# musicbusinesscard.net
KiCad netlist of a schematic drawn in EAGLE
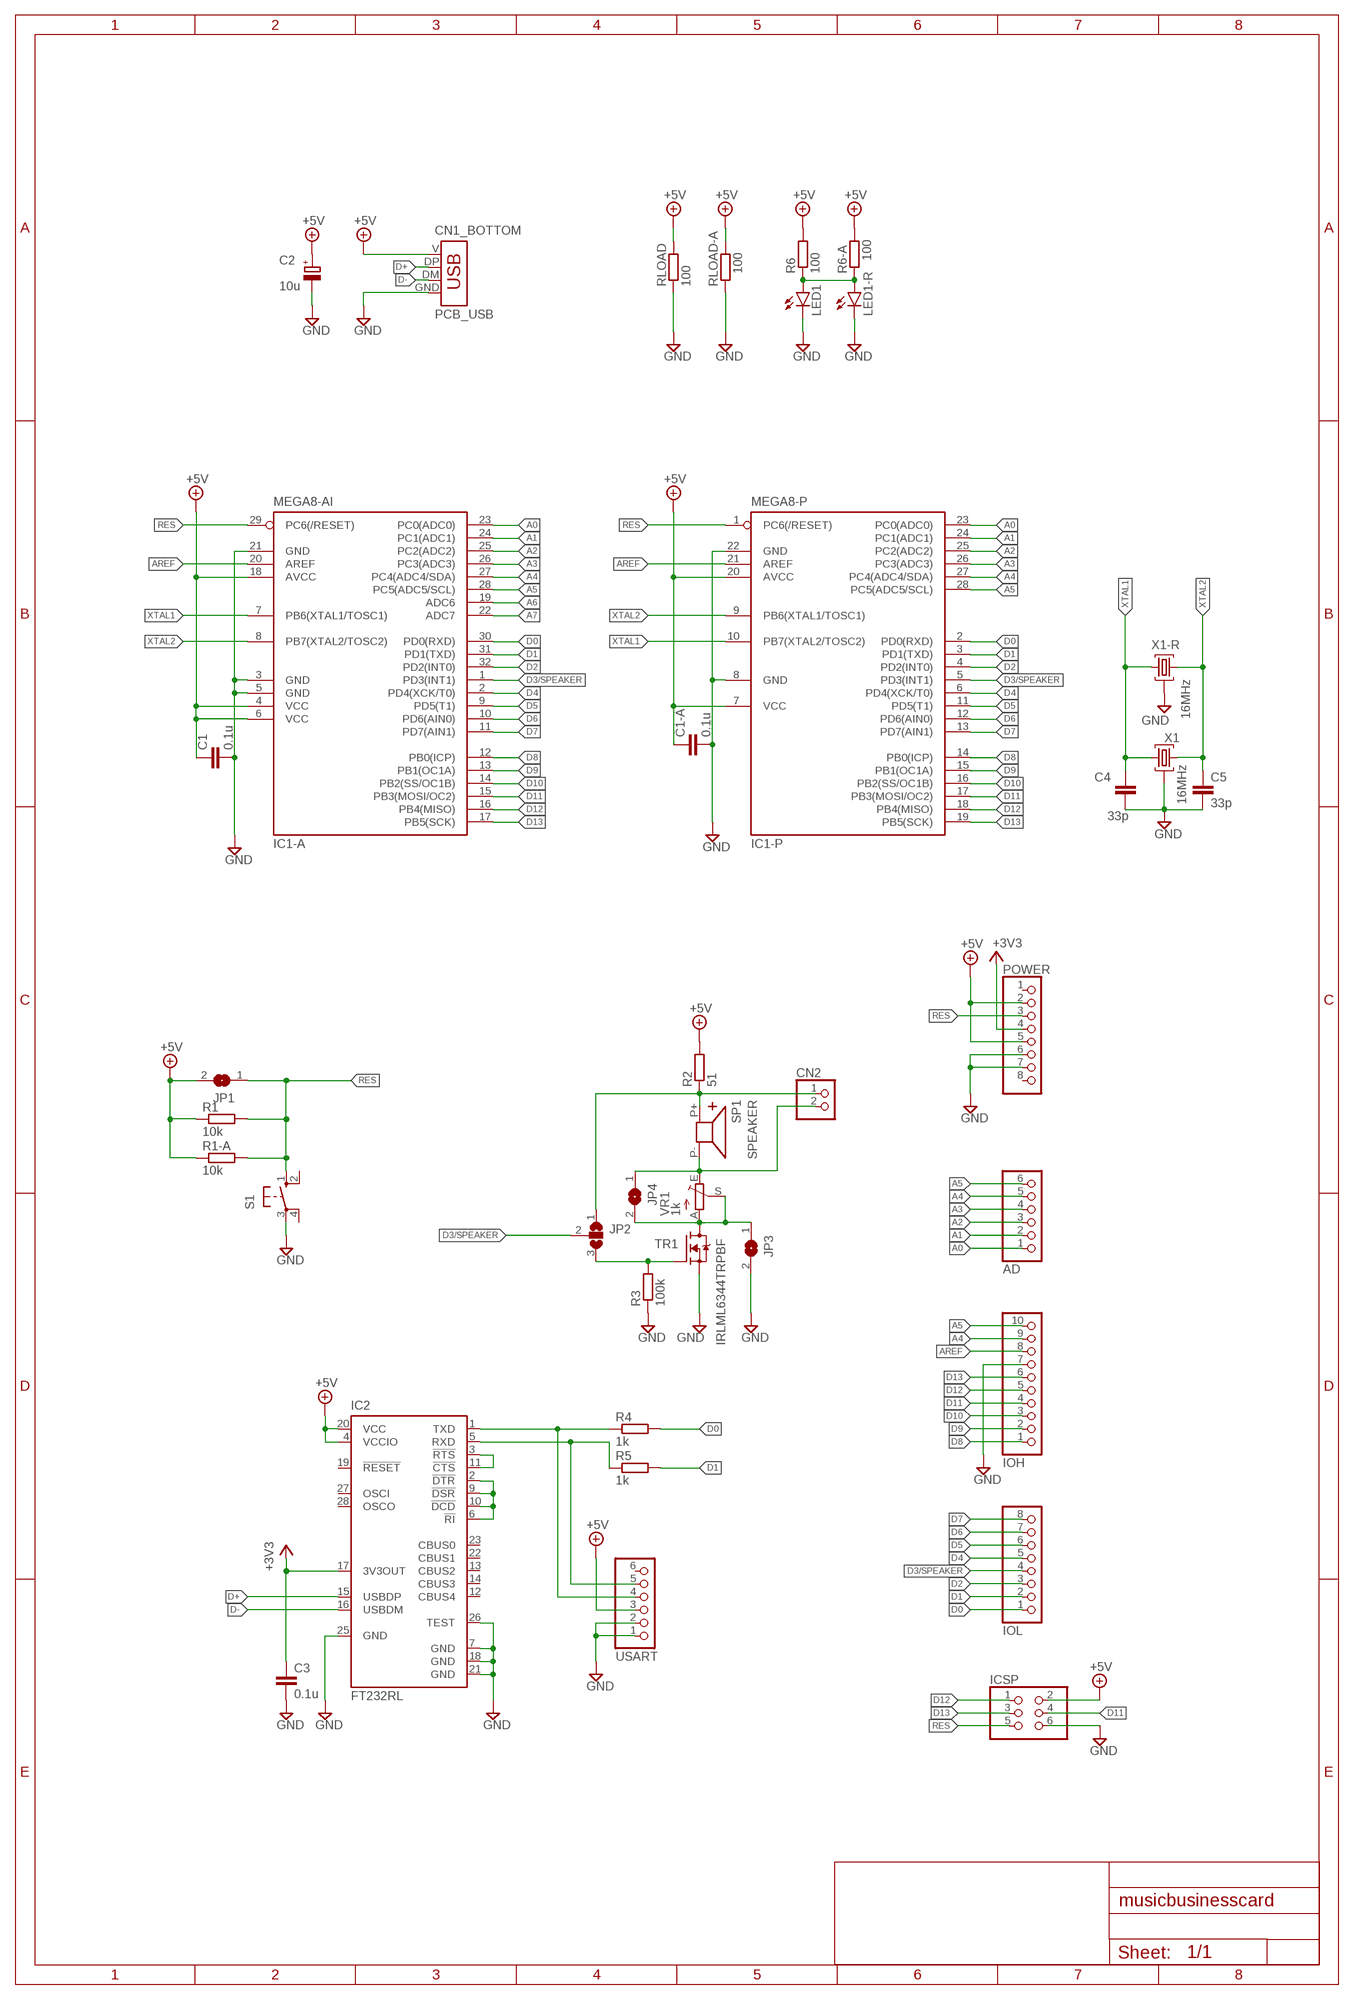
[diagram p0: schematic, sheet 1]

(export (version "E")
  (design (tool "Eeschema 10.0.6"))
  (components
    (comp (ref "AD")
      (value "PINHD-1X6")
      (footprint "eagle-import:1X06")
      (libsource (lib "eagle-import") (part "PINHD-1X6"))
    )
    (comp (ref "C1")
      (value "0.1u")
      (footprint "eagle-import:C3216")
      (libsource (lib "eagle-import") (part "C-EUC3216"))
    )
    (comp (ref "C1-A")
      (value "0.1u")
      (footprint "eagle-import:C050-024X044")
      (libsource (lib "eagle-import") (part "C-EU050-024X044"))
    )
    (comp (ref "C2")
      (value "10u")
      (footprint "eagle-import:TT2D5")
      (libsource (lib "eagle-import") (part "CPOL-EUTT2D5"))
    )
    (comp (ref "C3")
      (value "0.1u")
      (footprint "eagle-import:C3216")
      (libsource (lib "eagle-import") (part "C-EUC3216"))
    )
    (comp (ref "C4")
      (value "33p")
      (footprint "eagle-import:C050-024X044")
      (libsource (lib "eagle-import") (part "C-EU050-024X044"))
    )
    (comp (ref "C5")
      (value "33p")
      (footprint "eagle-import:C050-024X044")
      (libsource (lib "eagle-import") (part "C-EU050-024X044"))
    )
    (comp (ref "CN1_BOTTOM")
      (value "PCB_USB")
      (footprint "eagle-import:PCB_USB")
      (libsource (lib "eagle-import") (part "PCB_USB"))
    )
    (comp (ref "CN2")
      (value "PINHD-1X2")
      (footprint "eagle-import:1X02")
      (libsource (lib "eagle-import") (part "PINHD-1X2"))
    )
    (comp (ref "IC1-A")
      (value "MEGA8-AI")
      (footprint "eagle-import:TQFP32-08")
      (fields (field (name "MPN") "ATMEGA8-16AU"))
      (libsource (lib "eagle-import") (part "MEGA8-AI"))
    )
    (comp (ref "IC1-P")
      (value "MEGA8-P")
      (footprint "eagle-import:DIL28-3")
      (libsource (lib "eagle-import") (part "MEGA8-P"))
    )
    (comp (ref "IC2")
      (value "FT232RL")
      (footprint "eagle-import:SSOP28")
      (libsource (lib "eagle-import") (part "FT232RL"))
    )
    (comp (ref "ICSP")
      (value "PINHD-2X3")
      (footprint "eagle-import:2X03")
      (libsource (lib "eagle-import") (part "PINHD-2X3"))
    )
    (comp (ref "IOH")
      (value "PINHD-1X10")
      (footprint "eagle-import:1X10")
      (libsource (lib "eagle-import") (part "PINHD-1X10"))
    )
    (comp (ref "IOL")
      (value "PINHD-1X8")
      (footprint "eagle-import:1X08")
      (libsource (lib "eagle-import") (part "PINHD-1X8"))
    )
    (comp (ref "JP1") (value "SJ") (footprint "eagle-import:SJ") (libsource (lib "eagle-import") (part "SJ")))
    (comp (ref "JP2")
      (value "SJ2W")
      (footprint "eagle-import:SJ_2")
      (libsource (lib "eagle-import") (part "SJ2W"))
    )
    (comp (ref "JP3") (value "SJ") (footprint "eagle-import:SJ") (libsource (lib "eagle-import") (part "SJ")))
    (comp (ref "JP4") (value "SJ") (footprint "eagle-import:SJ") (libsource (lib "eagle-import") (part "SJ")))
    (comp (ref "LED1")
      (value "LEDCHIPLED_1206")
      (footprint "eagle-import:CHIPLED_1206")
      (libsource (lib "eagle-import") (part "LEDCHIPLED_1206"))
    )
    (comp (ref "LED1-R")
      (value "LED3MM")
      (footprint "eagle-import:LED3MM")
      (libsource (lib "eagle-import") (part "LED3MM"))
    )
    (comp (ref "POWER")
      (value "PINHD-1X8")
      (footprint "eagle-import:1X08")
      (libsource (lib "eagle-import") (part "PINHD-1X8"))
    )
    (comp (ref "R1")
      (value "10k")
      (footprint "eagle-import:R3216")
      (libsource (lib "eagle-import") (part "R-EU_R3216"))
    )
    (comp (ref "R1-A")
      (value "10k")
      (footprint "eagle-import:0207_10")
      (libsource (lib "eagle-import") (part "R-EU_0207/10"))
    )
    (comp (ref "R2")
      (value "51")
      (footprint "eagle-import:R3216")
      (libsource (lib "eagle-import") (part "R-EU_R3216"))
    )
    (comp (ref "R3")
      (value "100k")
      (footprint "eagle-import:R3216")
      (libsource (lib "eagle-import") (part "R-EU_R3216"))
    )
    (comp (ref "R4")
      (value "1k")
      (footprint "eagle-import:R3216")
      (libsource (lib "eagle-import") (part "R-EU_R3216"))
    )
    (comp (ref "R5")
      (value "1k")
      (footprint "eagle-import:R3216")
      (libsource (lib "eagle-import") (part "R-EU_R3216"))
    )
    (comp (ref "R6")
      (value "100")
      (footprint "eagle-import:R3216")
      (libsource (lib "eagle-import") (part "R-EU_R3216"))
    )
    (comp (ref "R6-A")
      (value "100")
      (footprint "eagle-import:0207_10")
      (libsource (lib "eagle-import") (part "R-EU_0207/10"))
    )
    (comp (ref "RLOAD")
      (value "100")
      (footprint "eagle-import:R3216")
      (libsource (lib "eagle-import") (part "R-EU_R3216"))
    )
    (comp (ref "RLOAD-A")
      (value "100")
      (footprint "eagle-import:0207_10")
      (libsource (lib "eagle-import") (part "R-EU_0207/10"))
    )
    (comp (ref "S1")
      (value "10-XX")
      (footprint "eagle-import:B3F-10XX")
      (fields (field (name "MPN") "B3F-1000"))
      (libsource (lib "eagle-import") (part "10-XX"))
    )
    (comp (ref "SP1")
      (value "SPEAKER")
      (footprint "eagle-import:SPEAKER")
      (libsource (lib "eagle-import") (part "SPEAKER"))
    )
    (comp (ref "TR1")
      (value "IRLML6344TRPBF")
      (footprint "eagle-import:SOT23")
      (libsource (lib "eagle-import") (part "IRLML6344TRPBF"))
    )
    (comp (ref "USART")
      (value "PINHD-1X6")
      (footprint "eagle-import:1X06")
      (libsource (lib "eagle-import") (part "PINHD-1X6"))
    )
    (comp (ref "VR1")
      (value "1k")
      (footprint "eagle-import:B25P")
      (libsource (lib "eagle-import") (part "TRIM_EU-B25P"))
    )
    (comp (ref "X1")
      (value "16MHz")
      (footprint "eagle-import:XTAL_MURATA")
      (libsource (lib "eagle-import") (part "XTAL_MURATA"))
    )
    (comp (ref "X1-R")
      (value "16MHz")
      (footprint "eagle-import:HC49U")
      (libsource (lib "eagle-import") (part "14M20BHC49T"))
    )
  )
  (nets
    (net (code "1") (name "+3V3") (class "Default")
      (node (ref "C3") (pin "1") (pinfunction "1_1") (pintype "passive"))
      (node (ref "IC2") (pin "17") (pinfunction "3V3OUT_17") (pintype "output"))
      (node (ref "POWER") (pin "4") (pinfunction "4_4") (pintype "passive"))
    )
    (net (code "2") (name "+5V") (class "Default")
      (node (ref "C1") (pin "1") (pinfunction "1_1") (pintype "passive"))
      (node (ref "C1-A") (pin "1") (pinfunction "1_1") (pintype "passive"))
      (node (ref "C2") (pin "+") (pinfunction "+_+") (pintype "passive"))
      (node (ref "CN1_BOTTOM") (pin "V") (pinfunction "1_V") (pintype "passive"))
      (node (ref "IC1-A") (pin "18") (pinfunction "AVCC_18") (pintype "power_in"))
      (node (ref "IC1-A") (pin "4") (pinfunction "VCC_4") (pintype "power_in"))
      (node (ref "IC1-A") (pin "6") (pinfunction "VCC_6") (pintype "power_in"))
      (node (ref "IC1-P") (pin "20") (pinfunction "AVCC_20") (pintype "power_in"))
      (node (ref "IC1-P") (pin "7") (pinfunction "VCC_7") (pintype "power_in"))
      (node (ref "IC2") (pin "20") (pinfunction "VCC_20") (pintype "power_in"))
      (node (ref "IC2") (pin "4") (pinfunction "VCCIO_4") (pintype "power_in"))
      (node (ref "ICSP") (pin "2") (pinfunction "2_2") (pintype "passive"))
      (node (ref "JP1") (pin "2") (pinfunction "2_2") (pintype "passive"))
      (node (ref "POWER") (pin "2") (pinfunction "2_2") (pintype "passive"))
      (node (ref "POWER") (pin "5") (pinfunction "5_5") (pintype "passive"))
      (node (ref "R1") (pin "1") (pinfunction "1_1") (pintype "passive"))
      (node (ref "R1-A") (pin "1") (pinfunction "1_1") (pintype "passive"))
      (node (ref "R2") (pin "2") (pinfunction "2_2") (pintype "passive"))
      (node (ref "R6") (pin "2") (pinfunction "2_2") (pintype "passive"))
      (node (ref "R6-A") (pin "2") (pinfunction "2_2") (pintype "passive"))
      (node (ref "RLOAD") (pin "2") (pinfunction "2_2") (pintype "passive"))
      (node (ref "RLOAD-A") (pin "2") (pinfunction "2_2") (pintype "passive"))
      (node (ref "USART") (pin "3") (pinfunction "3_3") (pintype "passive"))
    )
    (net (code "3") (name "A0") (class "Default")
      (node (ref "AD") (pin "1") (pinfunction "1_1") (pintype "passive"))
      (node (ref "IC1-A") (pin "23") (pinfunction "PC0(ADC0)_23") (pintype "bidirectional"))
      (node (ref "IC1-P") (pin "23") (pinfunction "PC0(ADC0)_23") (pintype "bidirectional"))
    )
    (net (code "4") (name "A1") (class "Default")
      (node (ref "AD") (pin "2") (pinfunction "2_2") (pintype "passive"))
      (node (ref "IC1-A") (pin "24") (pinfunction "PC1(ADC1)_24") (pintype "bidirectional"))
      (node (ref "IC1-P") (pin "24") (pinfunction "PC1(ADC1)_24") (pintype "bidirectional"))
    )
    (net (code "5") (name "A2") (class "Default")
      (node (ref "AD") (pin "3") (pinfunction "3_3") (pintype "passive"))
      (node (ref "IC1-A") (pin "25") (pinfunction "PC2(ADC2)_25") (pintype "bidirectional"))
      (node (ref "IC1-P") (pin "25") (pinfunction "PC2(ADC2)_25") (pintype "bidirectional"))
    )
    (net (code "6") (name "A3") (class "Default")
      (node (ref "AD") (pin "4") (pinfunction "4_4") (pintype "passive"))
      (node (ref "IC1-A") (pin "26") (pinfunction "PC3(ADC3)_26") (pintype "bidirectional"))
      (node (ref "IC1-P") (pin "26") (pinfunction "PC3(ADC3)_26") (pintype "bidirectional"))
    )
    (net (code "7") (name "A4") (class "Default")
      (node (ref "AD") (pin "5") (pinfunction "5_5") (pintype "passive"))
      (node (ref "IC1-A") (pin "27") (pinfunction "PC4(ADC4/SDA)_27") (pintype "bidirectional"))
      (node (ref "IC1-P") (pin "27") (pinfunction "PC4(ADC4/SDA)_27") (pintype "bidirectional"))
      (node (ref "IOH") (pin "9") (pinfunction "9_9") (pintype "passive"))
    )
    (net (code "8") (name "A5") (class "Default")
      (node (ref "AD") (pin "6") (pinfunction "6_6") (pintype "passive"))
      (node (ref "IC1-A") (pin "28") (pinfunction "PC5(ADC5/SCL)_28") (pintype "bidirectional"))
      (node (ref "IC1-P") (pin "28") (pinfunction "PC5(ADC5/SCL)_28") (pintype "bidirectional"))
      (node (ref "IOH") (pin "10") (pinfunction "10_10") (pintype "passive"))
    )
    (net (code "9") (name "A6") (class "Default")
      (node (ref "IC1-A") (pin "19") (pinfunction "ADC6_19") (pintype "bidirectional"))
    )
    (net (code "10") (name "A7") (class "Default")
      (node (ref "IC1-A") (pin "22") (pinfunction "ADC7_22") (pintype "bidirectional"))
    )
    (net (code "11") (name "AREF") (class "Default")
      (node (ref "IC1-A") (pin "20") (pinfunction "AREF_20") (pintype "passive"))
      (node (ref "IC1-P") (pin "21") (pinfunction "AREF_21") (pintype "passive"))
      (node (ref "IOH") (pin "8") (pinfunction "8_8") (pintype "passive"))
    )
    (net (code "12") (name "D+") (class "Default")
      (node (ref "CN1_BOTTOM") (pin "DP") (pinfunction "2_DP") (pintype "passive"))
      (node (ref "IC2") (pin "15") (pinfunction "USBDP_15") (pintype "bidirectional"))
    )
    (net (code "13") (name "D-") (class "Default")
      (node (ref "CN1_BOTTOM") (pin "DM") (pinfunction "3_DM") (pintype "passive"))
      (node (ref "IC2") (pin "16") (pinfunction "USBDM_16") (pintype "bidirectional"))
    )
    (net (code "14") (name "D0") (class "Default")
      (node (ref "IC1-A") (pin "30") (pinfunction "PD0(RXD)_30") (pintype "bidirectional"))
      (node (ref "IC1-P") (pin "2") (pinfunction "PD0(RXD)_2") (pintype "bidirectional"))
      (node (ref "IOL") (pin "1") (pinfunction "1_1") (pintype "passive"))
      (node (ref "R4") (pin "2") (pinfunction "2_2") (pintype "passive"))
    )
    (net (code "15") (name "D1") (class "Default")
      (node (ref "IC1-A") (pin "31") (pinfunction "PD1(TXD)_31") (pintype "bidirectional"))
      (node (ref "IC1-P") (pin "3") (pinfunction "PD1(TXD)_3") (pintype "bidirectional"))
      (node (ref "IOL") (pin "2") (pinfunction "2_2") (pintype "passive"))
      (node (ref "R5") (pin "2") (pinfunction "2_2") (pintype "passive"))
    )
    (net (code "16") (name "D2") (class "Default")
      (node (ref "IC1-A") (pin "32") (pinfunction "PD2(INT0)_32") (pintype "bidirectional"))
      (node (ref "IC1-P") (pin "4") (pinfunction "PD2(INT0)_4") (pintype "bidirectional"))
      (node (ref "IOL") (pin "3") (pinfunction "3_3") (pintype "passive"))
    )
    (net (code "17") (name "D3{slash}SPEAKER") (class "Default")
      (node (ref "IC1-A") (pin "1") (pinfunction "PD3(INT1)_1") (pintype "bidirectional"))
      (node (ref "IC1-P") (pin "5") (pinfunction "PD3(INT1)_5") (pintype "bidirectional"))
      (node (ref "IOL") (pin "4") (pinfunction "4_4") (pintype "passive"))
      (node (ref "JP2") (pin "2") (pinfunction "2_2") (pintype "passive"))
    )
    (net (code "18") (name "D4") (class "Default")
      (node (ref "IC1-A") (pin "2") (pinfunction "PD4(XCK/T0)_2") (pintype "bidirectional"))
      (node (ref "IC1-P") (pin "6") (pinfunction "PD4(XCK/T0)_6") (pintype "bidirectional"))
      (node (ref "IOL") (pin "5") (pinfunction "5_5") (pintype "passive"))
    )
    (net (code "19") (name "D5") (class "Default")
      (node (ref "IC1-A") (pin "9") (pinfunction "PD5(T1)_9") (pintype "bidirectional"))
      (node (ref "IC1-P") (pin "11") (pinfunction "PD5(T1)_11") (pintype "bidirectional"))
      (node (ref "IOL") (pin "6") (pinfunction "6_6") (pintype "passive"))
    )
    (net (code "20") (name "D6") (class "Default")
      (node (ref "IC1-A") (pin "10") (pinfunction "PD6(AIN0)_10") (pintype "bidirectional"))
      (node (ref "IC1-P") (pin "12") (pinfunction "PD6(AIN0)_12") (pintype "bidirectional"))
      (node (ref "IOL") (pin "7") (pinfunction "7_7") (pintype "passive"))
    )
    (net (code "21") (name "D7") (class "Default")
      (node (ref "IC1-A") (pin "11") (pinfunction "PD7(AIN1)_11") (pintype "bidirectional"))
      (node (ref "IC1-P") (pin "13") (pinfunction "PD7(AIN1)_13") (pintype "bidirectional"))
      (node (ref "IOL") (pin "8") (pinfunction "8_8") (pintype "passive"))
    )
    (net (code "22") (name "D8") (class "Default")
      (node (ref "IC1-A") (pin "12") (pinfunction "PB0(ICP)_12") (pintype "bidirectional"))
      (node (ref "IC1-P") (pin "14") (pinfunction "PB0(ICP)_14") (pintype "bidirectional"))
      (node (ref "IOH") (pin "1") (pinfunction "1_1") (pintype "passive"))
    )
    (net (code "23") (name "D9") (class "Default")
      (node (ref "IC1-A") (pin "13") (pinfunction "PB1(OC1A)_13") (pintype "bidirectional"))
      (node (ref "IC1-P") (pin "15") (pinfunction "PB1(OC1A)_15") (pintype "bidirectional"))
      (node (ref "IOH") (pin "2") (pinfunction "2_2") (pintype "passive"))
    )
    (net (code "24") (name "D10") (class "Default")
      (node (ref "IC1-A") (pin "14") (pinfunction "PB2(SS/OC1B)_14") (pintype "bidirectional"))
      (node (ref "IC1-P") (pin "16") (pinfunction "PB2(SS/OC1B)_16") (pintype "bidirectional"))
      (node (ref "IOH") (pin "3") (pinfunction "3_3") (pintype "passive"))
    )
    (net (code "25") (name "D11") (class "Default")
      (node (ref "IC1-A") (pin "15") (pinfunction "PB3(MOSI/OC2)_15") (pintype "bidirectional"))
      (node (ref "IC1-P") (pin "17") (pinfunction "PB3(MOSI/OC2)_17") (pintype "bidirectional"))
      (node (ref "ICSP") (pin "4") (pinfunction "4_4") (pintype "passive"))
      (node (ref "IOH") (pin "4") (pinfunction "4_4") (pintype "passive"))
    )
    (net (code "26") (name "D12") (class "Default")
      (node (ref "IC1-A") (pin "16") (pinfunction "PB4(MISO)_16") (pintype "bidirectional"))
      (node (ref "IC1-P") (pin "18") (pinfunction "PB4(MISO)_18") (pintype "bidirectional"))
      (node (ref "ICSP") (pin "1") (pinfunction "1_1") (pintype "passive"))
      (node (ref "IOH") (pin "5") (pinfunction "5_5") (pintype "passive"))
    )
    (net (code "27") (name "D13") (class "Default")
      (node (ref "IC1-A") (pin "17") (pinfunction "PB5(SCK)_17") (pintype "bidirectional"))
      (node (ref "IC1-P") (pin "19") (pinfunction "PB5(SCK)_19") (pintype "bidirectional"))
      (node (ref "ICSP") (pin "3") (pinfunction "3_3") (pintype "passive"))
      (node (ref "IOH") (pin "6") (pinfunction "6_6") (pintype "passive"))
    )
    (net (code "28") (name "GND") (class "Default")
      (node (ref "C1") (pin "2") (pinfunction "2_2") (pintype "passive"))
      (node (ref "C1-A") (pin "2") (pinfunction "2_2") (pintype "passive"))
      (node (ref "C2") (pin "-") (pinfunction "-_-") (pintype "passive"))
      (node (ref "C3") (pin "2") (pinfunction "2_2") (pintype "passive"))
      (node (ref "C4") (pin "2") (pinfunction "2_2") (pintype "passive"))
      (node (ref "C5") (pin "2") (pinfunction "2_2") (pintype "passive"))
      (node (ref "CN1_BOTTOM") (pin "GND") (pinfunction "4_GND") (pintype "passive"))
      (node (ref "IC1-A") (pin "21") (pinfunction "GND_21") (pintype "power_in"))
      (node (ref "IC1-A") (pin "3") (pinfunction "GND_3") (pintype "power_in"))
      (node (ref "IC1-A") (pin "5") (pinfunction "GND_5") (pintype "power_in"))
      (node (ref "IC1-P") (pin "22") (pinfunction "GND_22") (pintype "power_in"))
      (node (ref "IC1-P") (pin "8") (pinfunction "GND_8") (pintype "power_in"))
      (node (ref "IC2") (pin "18") (pinfunction "GND_18") (pintype "power_in"))
      (node (ref "IC2") (pin "21") (pinfunction "GND_21") (pintype "power_in"))
      (node (ref "IC2") (pin "25") (pinfunction "GND_25") (pintype "power_in"))
      (node (ref "IC2") (pin "26") (pinfunction "TEST_26") (pintype "input"))
      (node (ref "IC2") (pin "7") (pinfunction "GND_7") (pintype "power_in"))
      (node (ref "ICSP") (pin "6") (pinfunction "6_6") (pintype "passive"))
      (node (ref "IOH") (pin "7") (pinfunction "7_7") (pintype "passive"))
      (node (ref "JP3") (pin "2") (pinfunction "2_2") (pintype "passive"))
      (node (ref "LED1") (pin "C") (pinfunction "C_C") (pintype "passive"))
      (node (ref "LED1-R") (pin "K") (pinfunction "C_K") (pintype "passive"))
      (node (ref "POWER") (pin "6") (pinfunction "6_6") (pintype "passive"))
      (node (ref "POWER") (pin "7") (pinfunction "7_7") (pintype "passive"))
      (node (ref "R3") (pin "1") (pinfunction "1_1") (pintype "passive"))
      (node (ref "RLOAD") (pin "1") (pinfunction "1_1") (pintype "passive"))
      (node (ref "RLOAD-A") (pin "1") (pinfunction "1_1") (pintype "passive"))
      (node (ref "S1") (pin "3") (pinfunction "P_3") (pintype "passive"))
      (node (ref "TR1") (pin "2") (pinfunction "S_2") (pintype "passive"))
      (node (ref "USART") (pin "1") (pinfunction "1_1") (pintype "passive"))
      (node (ref "USART") (pin "2") (pinfunction "2_2") (pintype "passive"))
      (node (ref "X1") (pin "2") (pinfunction "2_2") (pintype "passive"))
      (node (ref "X1-R") (pin "2") (pinfunction "2_2") (pintype "passive"))
    )
    (net (code "29") (name "Net-(IC2-RXD)") (class "Default")
      (node (ref "IC2") (pin "5") (pinfunction "RXD_5") (pintype "input"))
      (node (ref "R5") (pin "1") (pinfunction "1_1") (pintype "passive"))
      (node (ref "USART") (pin "5") (pinfunction "5_5") (pintype "passive"))
    )
    (net (code "30") (name "Net-(IC2-TXD)") (class "Default")
      (node (ref "IC2") (pin "1") (pinfunction "TXD_1") (pintype "output"))
      (node (ref "R4") (pin "1") (pinfunction "1_1") (pintype "passive"))
      (node (ref "USART") (pin "4") (pinfunction "4_4") (pintype "passive"))
    )
    (net (code "31") (name "Net-(IC2-~{CTS})") (class "Default")
      (node (ref "IC2") (pin "11") (pinfunction "~{CTS}_11") (pintype "input"))
      (node (ref "IC2") (pin "3") (pinfunction "~{RTS}_3") (pintype "output"))
    )
    (net (code "32") (name "Net-(IC2-~{DCD})") (class "Default")
      (node (ref "IC2") (pin "10") (pinfunction "~{DCD}_10") (pintype "input"))
      (node (ref "IC2") (pin "2") (pinfunction "~{DTR}_2") (pintype "output"))
      (node (ref "IC2") (pin "6") (pinfunction "~{RI}_6") (pintype "input"))
      (node (ref "IC2") (pin "9") (pinfunction "~{DSR}_9") (pintype "input"))
    )
    (net (code "33") (name "Net-(LED1-PadA)") (class "Default")
      (node (ref "LED1") (pin "A") (pinfunction "A_A") (pintype "passive"))
      (node (ref "LED1-R") (pin "A") (pinfunction "A_A") (pintype "passive"))
      (node (ref "R6") (pin "1") (pinfunction "1_1") (pintype "passive"))
      (node (ref "R6-A") (pin "1") (pinfunction "1_1") (pintype "passive"))
    )
    (net (code "34") (name "Net-(SP1-1)") (class "Default")
      (node (ref "CN2") (pin "1") (pinfunction "1_1") (pintype "passive"))
      (node (ref "JP2") (pin "1") (pinfunction "1_1") (pintype "passive"))
      (node (ref "R2") (pin "1") (pinfunction "1_1") (pintype "passive"))
      (node (ref "SP1") (pin "P+") (pinfunction "1_P+") (pintype "passive"))
    )
    (net (code "35") (name "Net-(SP1-2)") (class "Default")
      (node (ref "CN2") (pin "2") (pinfunction "2_2") (pintype "passive"))
      (node (ref "JP4") (pin "1") (pinfunction "1_1") (pintype "passive"))
      (node (ref "SP1") (pin "P-") (pinfunction "2_P-") (pintype "passive"))
      (node (ref "VR1") (pin "E") (pinfunction "E_E") (pintype "passive"))
    )
    (net (code "36") (name "Net-(TR1-D)") (class "Default")
      (node (ref "JP3") (pin "1") (pinfunction "1_1") (pintype "passive"))
      (node (ref "JP4") (pin "2") (pinfunction "2_2") (pintype "passive"))
      (node (ref "TR1") (pin "3") (pinfunction "D_3") (pintype "passive"))
      (node (ref "VR1") (pin "A") (pinfunction "A_A") (pintype "passive"))
      (node (ref "VR1") (pin "S") (pinfunction "S_S") (pintype "passive"))
    )
    (net (code "37") (name "Net-(TR1-G)") (class "Default")
      (node (ref "JP2") (pin "3") (pinfunction "3_3") (pintype "passive"))
      (node (ref "R3") (pin "2") (pinfunction "2_2") (pintype "passive"))
      (node (ref "TR1") (pin "1") (pinfunction "G_1") (pintype "passive"))
    )
    (net (code "38") (name "RES") (class "Default")
      (node (ref "IC1-A") (pin "29") (pinfunction "PC6(/RESET)_29") (pintype "bidirectional"))
      (node (ref "IC1-P") (pin "1") (pinfunction "PC6(/RESET)_1") (pintype "bidirectional"))
      (node (ref "ICSP") (pin "5") (pinfunction "5_5") (pintype "passive"))
      (node (ref "JP1") (pin "1") (pinfunction "1_1") (pintype "passive"))
      (node (ref "POWER") (pin "3") (pinfunction "3_3") (pintype "passive"))
      (node (ref "R1") (pin "2") (pinfunction "2_2") (pintype "passive"))
      (node (ref "R1-A") (pin "2") (pinfunction "2_2") (pintype "passive"))
      (node (ref "S1") (pin "1") (pinfunction "S_1") (pintype "passive"))
    )
    (net (code "39") (name "XTAL1") (class "Default")
      (node (ref "C4") (pin "1") (pinfunction "1_1") (pintype "passive"))
      (node (ref "IC1-A") (pin "7") (pinfunction "PB6(XTAL1/TOSC1)_7") (pintype "bidirectional"))
      (node (ref "IC1-P") (pin "10") (pinfunction "PB7(XTAL2/TOSC2)_10") (pintype "bidirectional"))
      (node (ref "X1") (pin "1") (pinfunction "1_1") (pintype "passive"))
      (node (ref "X1-R") (pin "1") (pinfunction "1_1") (pintype "passive"))
    )
    (net (code "40") (name "XTAL2") (class "Default")
      (node (ref "C5") (pin "1") (pinfunction "1_1") (pintype "passive"))
      (node (ref "IC1-A") (pin "8") (pinfunction "PB7(XTAL2/TOSC2)_8") (pintype "bidirectional"))
      (node (ref "IC1-P") (pin "9") (pinfunction "PB6(XTAL1/TOSC1)_9") (pintype "bidirectional"))
      (node (ref "X1") (pin "3") (pinfunction "3_3") (pintype "passive"))
      (node (ref "X1-R") (pin "3") (pinfunction "3_3") (pintype "passive"))
    )
    (net (code "41") (name "unconnected-(IC2-CBUS0-Pad23)") (class "Default")
      (node (ref "IC2") (pin "23") (pinfunction "CBUS0_23") (pintype "bidirectional"))
    )
    (net (code "42") (name "unconnected-(IC2-CBUS1-Pad22)") (class "Default")
      (node (ref "IC2") (pin "22") (pinfunction "CBUS1_22") (pintype "bidirectional"))
    )
    (net (code "43") (name "unconnected-(IC2-CBUS2-Pad13)") (class "Default")
      (node (ref "IC2") (pin "13") (pinfunction "CBUS2_13") (pintype "bidirectional"))
    )
    (net (code "44") (name "unconnected-(IC2-CBUS3-Pad14)") (class "Default")
      (node (ref "IC2") (pin "14") (pinfunction "CBUS3_14") (pintype "bidirectional"))
    )
    (net (code "45") (name "unconnected-(IC2-CBUS4-Pad12)") (class "Default")
      (node (ref "IC2") (pin "12") (pinfunction "CBUS4_12") (pintype "bidirectional"))
    )
    (net (code "46") (name "unconnected-(IC2-OSCI-Pad27)") (class "Default")
      (node (ref "IC2") (pin "27") (pinfunction "OSCI_27") (pintype "input"))
    )
    (net (code "47") (name "unconnected-(IC2-OSCO-Pad28)") (class "Default")
      (node (ref "IC2") (pin "28") (pinfunction "OSCO_28") (pintype "output"))
    )
    (net (code "48") (name "unconnected-(IC2-~{RESET}-Pad19)") (class "Default")
      (node (ref "IC2") (pin "19") (pinfunction "~{RESET}_19") (pintype "input"))
    )
    (net (code "49") (name "unconnected-(POWER-Pad1)") (class "Default")
      (node (ref "POWER") (pin "1") (pinfunction "1_1") (pintype "passive"))
    )
    (net (code "50") (name "unconnected-(POWER-Pad8)") (class "Default")
      (node (ref "POWER") (pin "8") (pinfunction "8_8") (pintype "passive"))
    )
    (net (code "51") (name "unconnected-(S1-P1-Pad4)") (class "Default")
      (node (ref "S1") (pin "4") (pinfunction "P1_4") (pintype "passive"))
    )
    (net (code "52") (name "unconnected-(S1-S1-Pad2)") (class "Default")
      (node (ref "S1") (pin "2") (pinfunction "S1_2") (pintype "passive"))
    )
    (net (code "53") (name "unconnected-(USART-Pad6)") (class "Default")
      (node (ref "USART") (pin "6") (pinfunction "6_6") (pintype "passive"))
    )
  )
)
